# Ak_m_Alg_lama.net
KiCad netlist of a schematic drawn in Altium Designer
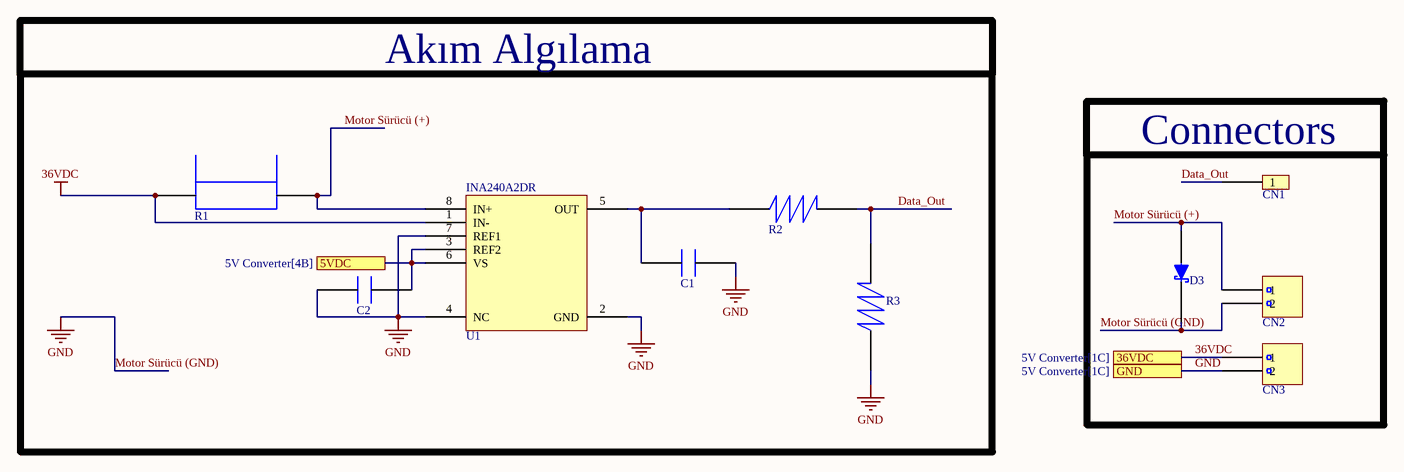
[diagram p0: Akım Algılama.SchDoc]

(export (version "E")
  (design (tool "Eeschema 10.0.6"))
  (components
    (comp (ref "C1")
      (value "CC0402KPX7R9BB104")
      (footprint "CAP_1005")
      (description "CAP 0402 50V 100 NF X7R")
      (fields (field (name "MANUFACTURER") "Yageo") (field (name "DESIGNED BY") "ismet Akalın"))
      (libsource (lib "shunt") (part "CC0402KPX7R9BB104"))
    )
    (comp (ref "C2")
      (value "CC0402KPX7R9BB104")
      (footprint "CAP_1005")
      (description "CAP 0402 50V 100 NF X7R")
      (fields (field (name "MANUFACTURER") "Yageo") (field (name "DESIGNED BY") "ismet Akalın"))
      (libsource (lib "shunt") (part "CC0402KPX7R9BB104"))
    )
    (comp (ref "CN1")
      (value "TS-101-T-A")
      (footprint "TS-101-T-A")
      (description "CONN HEADER VERT 1POS")
      (fields (field (name "MANUFACTURER") "Samtec") (field (name "DESIGNED BY") "ismet Akalın"))
      (libsource (lib "shunt") (part "TS-101-T-A"))
    )
    (comp (ref "CN2")
      (value "1719192")
      (footprint "1719192")
      (description "TERM BLK 2POS SIDE ENT 7.5MM PCB")
      (fields
        (field (name "MANUFACTURER") "Phoenix Contact")
        (field (name "DESIGNED BY") "ismet Akalın")
        (field (name "SAFETY APPROVAL") "UL")
      )
      (libsource (lib "shunt") (part "1719192"))
    )
    (comp (ref "CN3")
      (value "1719192")
      (footprint "1719192")
      (description "TERM BLK 2POS SIDE ENT 7.5MM PCB")
      (fields
        (field (name "MANUFACTURER") "Phoenix Contact")
        (field (name "DESIGNED BY") "ismet Akalın")
        (field (name "SAFETY APPROVAL") "UL")
      )
      (libsource (lib "shunt") (part "1719192"))
    )
    (comp (ref "D3")
      (value "SS14")
      (footprint "SMA-2 (SS14)")
      (description "DIODE SCHOTTKY 40V 1A DO214AC")
      (fields
        (field (name "MANUFACTURER") "ON Semiconductor / Fairchild")
        (field (name "DESIGNED BY") "ismet Akalın")
      )
      (libsource (lib "shunt") (part "SS14"))
    )
    (comp (ref "R1")
      (value "FCSL110R005FER")
      (footprint "FCSL110")
      (description "RES 0.005 OHM 5W 4320 WIDE")
      (fields
        (field (name "MANUFACTURER") "Ohmite")
        (field (name "TOLERANCE") "1%")
        (field (name "DESIGNED BY") "ismet Akalın")
      )
      (libsource (lib "shunt") (part "FCSL110R005FER"))
    )
    (comp (ref "R2")
      (value "RC0201FR-0710KL")
      (footprint "RES_0603")
      (description "RES 10K OHM 1% 1/20W 0201")
      (fields
        (field (name "MANUFACTURER") "Yageo")
        (field (name "MANUFACTURER PART NUMBER") "RC0201FR-07100KL")
        (field (name "DESIGNED BY") "ismet Akalın")
      )
      (libsource (lib "shunt") (part "RC0201FR-0710KL"))
    )
    (comp (ref "R3")
      (value "RC0603FR-106K8L")
      (footprint "RES_0603")
      (description "RES 6.8K OHM 1% 1/10W 0603")
      (fields
        (field (name "MANUFACTURER") "Yageo")
        (field (name "TOLERANCE") "1%")
        (field (name "DESIGNED BY") "ismet Akalın")
      )
      (libsource (lib "shunt") (part "RC0603FR-106K8L"))
    )
    (comp (ref "U1")
      (value "INA240A2DR")
      (footprint "SOIC8")
      (description "IC CURRENT SENSE 1 CIRCUIT 8SOIC")
      (fields
        (field (name "MANUFACTURER") "Texas Instruments")
        (field (name "MANUFACTURER PART NUMBER") "INA240A2DR")
        (field (name "DESIGNED BY") "ismet Akalın")
      )
      (libsource (lib "shunt") (part "INA240A2DR"))
    )
  )
  (nets
    (net (code "1") (name "/5VDC") (class "Default")
      (node (ref "C2") (pin "1") (pinfunction "1_1") (pintype "passive"))
      (node (ref "U1") (pin "3") (pinfunction "REF2_3") (pintype "passive"))
      (node (ref "U1") (pin "6") (pinfunction "VS_6") (pintype "passive"))
    )
    (net (code "2") (name "/Data_Out") (class "Default")
      (node (ref "CN1") (pin "1") (pinfunction "1_1") (pintype "passive"))
      (node (ref "R2") (pin "2") (pinfunction "2_2") (pintype "passive"))
      (node (ref "R3") (pin "2") (pinfunction "2_2") (pintype "passive"))
    )
    (net (code "3") (name "/Motor Sürücü (+)") (class "Default")
      (node (ref "CN2") (pin "1") (pinfunction "1_1") (pintype "passive"))
      (node (ref "D3") (pin "2") (pinfunction "2_2") (pintype "passive"))
      (node (ref "R1") (pin "1") (pinfunction "1_1") (pintype "passive"))
      (node (ref "U1") (pin "8") (pinfunction "IN+_8") (pintype "passive"))
    )
    (net (code "4") (name "36VDC") (class "Default")
      (node (ref "CN3") (pin "1") (pinfunction "1_1") (pintype "passive"))
      (node (ref "R1") (pin "0") (pinfunction "0_0") (pintype "passive"))
      (node (ref "U1") (pin "1") (pinfunction "IN-_1") (pintype "passive"))
    )
    (net (code "5") (name "GND") (class "Default")
      (node (ref "C1") (pin "1") (pinfunction "1_1") (pintype "passive"))
      (node (ref "C2") (pin "2") (pinfunction "2_2") (pintype "passive"))
      (node (ref "CN2") (pin "2") (pinfunction "2_2") (pintype "passive"))
      (node (ref "CN3") (pin "2") (pinfunction "2_2") (pintype "passive"))
      (node (ref "D3") (pin "1") (pinfunction "1_1") (pintype "passive"))
      (node (ref "R3") (pin "1") (pinfunction "1_1") (pintype "passive"))
      (node (ref "U1") (pin "2") (pinfunction "GND_2") (pintype "passive"))
      (node (ref "U1") (pin "4") (pinfunction "NC_4") (pintype "passive"))
      (node (ref "U1") (pin "7") (pinfunction "REF1_7") (pintype "passive"))
    )
    (net (code "6") (name "Net-(U1-OUT)") (class "Default")
      (node (ref "C1") (pin "2") (pinfunction "2_2") (pintype "passive"))
      (node (ref "R2") (pin "1") (pinfunction "1_1") (pintype "passive"))
      (node (ref "U1") (pin "5") (pinfunction "OUT_5") (pintype "passive"))
    )
  )
)
